# Sheet1_1.net
KiCad netlist of a schematic drawn in Altium Designer
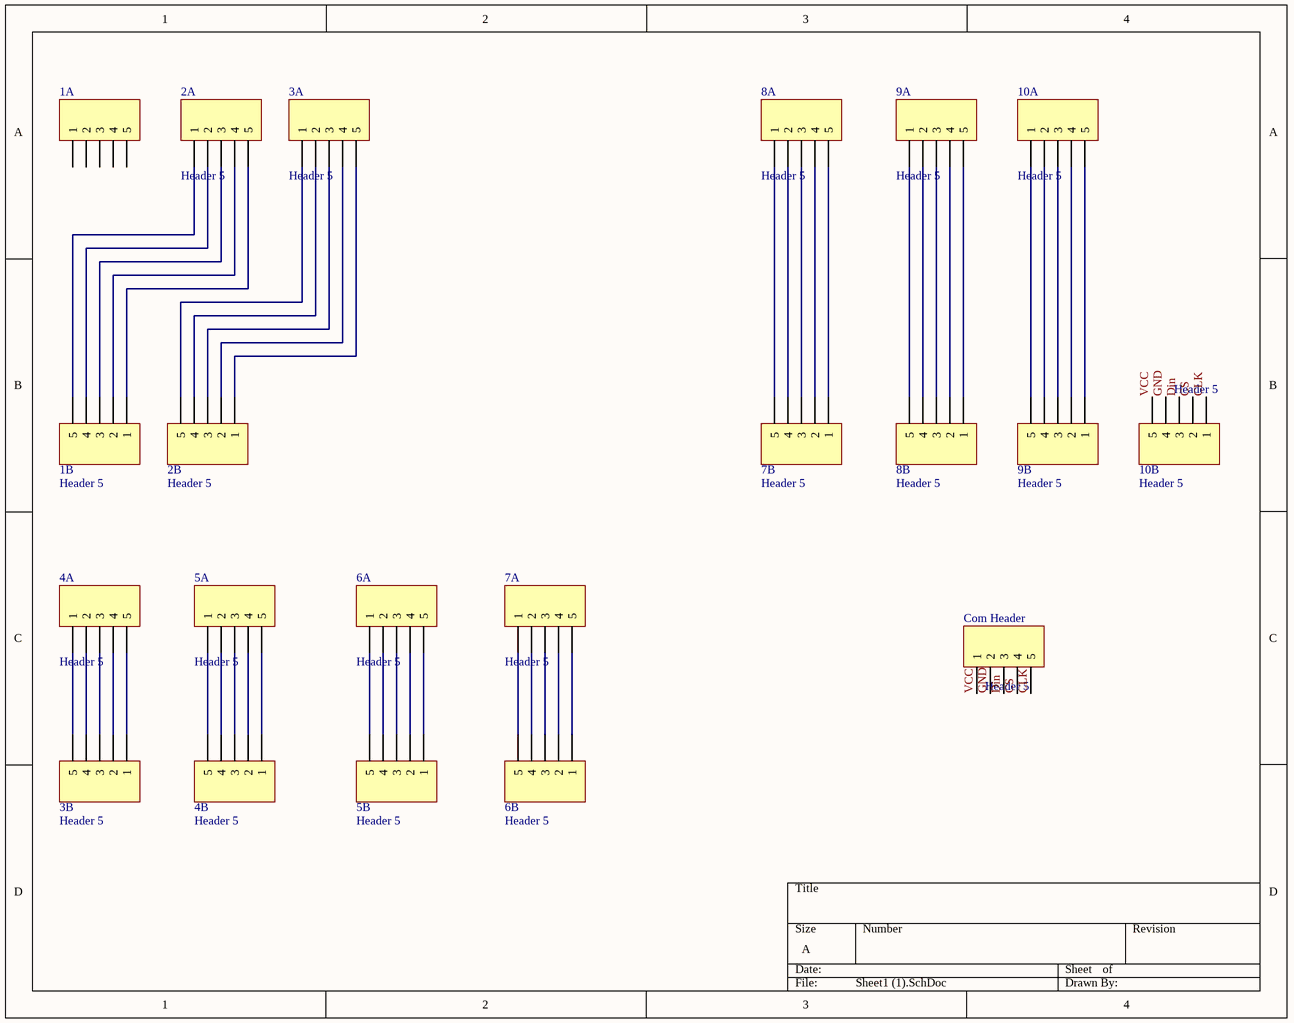
[diagram p0: Sheet1 (1).SchDoc]

(export (version "E")
  (design (tool "Eeschema 10.0.6"))
  (components
    (comp (ref "1A")
      (value "Header 5")
      (footprint "HDR1X5")
      (description "Header, 5-Pin")
      (fields (field (name "PUBLISHER") "Altium Limited"))
      (libsource (lib "Miscellaneous Connectors") (part "Header 5"))
    )
    (comp (ref "1B")
      (value "Header 5")
      (footprint "HDR1X5")
      (description "Header, 5-Pin")
      (fields (field (name "PUBLISHER") "Altium Limited"))
      (libsource (lib "") (part "Header 5_1"))
    )
    (comp (ref "2A")
      (value "Header 5")
      (footprint "HDR1X5")
      (description "Header, 5-Pin")
      (fields (field (name "PUBLISHER") "Altium Limited"))
      (libsource (lib "Miscellaneous Connectors") (part "Header 5"))
    )
    (comp (ref "2B")
      (value "Header 5")
      (footprint "HDR1X5")
      (description "Header, 5-Pin")
      (fields (field (name "PUBLISHER") "Altium Limited"))
      (libsource (lib "") (part "Header 5_1"))
    )
    (comp (ref "3A")
      (value "Header 5")
      (footprint "HDR1X5")
      (description "Header, 5-Pin")
      (fields (field (name "PUBLISHER") "Altium Limited"))
      (libsource (lib "Miscellaneous Connectors") (part "Header 5"))
    )
    (comp (ref "3B")
      (value "Header 5")
      (footprint "HDR1X5")
      (description "Header, 5-Pin")
      (fields (field (name "PUBLISHER") "Altium Limited"))
      (libsource (lib "") (part "Header 5_1"))
    )
    (comp (ref "4A")
      (value "Header 5")
      (footprint "HDR1X5")
      (description "Header, 5-Pin")
      (fields (field (name "PUBLISHER") "Altium Limited"))
      (libsource (lib "Miscellaneous Connectors") (part "Header 5"))
    )
    (comp (ref "4B")
      (value "Header 5")
      (footprint "HDR1X5")
      (description "Header, 5-Pin")
      (fields (field (name "PUBLISHER") "Altium Limited"))
      (libsource (lib "") (part "Header 5_1"))
    )
    (comp (ref "5A")
      (value "Header 5")
      (footprint "HDR1X5")
      (description "Header, 5-Pin")
      (fields (field (name "PUBLISHER") "Altium Limited"))
      (libsource (lib "Miscellaneous Connectors") (part "Header 5"))
    )
    (comp (ref "5B")
      (value "Header 5")
      (footprint "HDR1X5")
      (description "Header, 5-Pin")
      (fields (field (name "PUBLISHER") "Altium Limited"))
      (libsource (lib "") (part "Header 5_1"))
    )
    (comp (ref "6A")
      (value "Header 5")
      (footprint "HDR1X5")
      (description "Header, 5-Pin")
      (fields (field (name "PUBLISHER") "Altium Limited"))
      (libsource (lib "Miscellaneous Connectors") (part "Header 5"))
    )
    (comp (ref "6B")
      (value "Header 5")
      (footprint "HDR1X5")
      (description "Header, 5-Pin")
      (fields (field (name "PUBLISHER") "Altium Limited"))
      (libsource (lib "") (part "Header 5_1"))
    )
    (comp (ref "7A")
      (value "Header 5")
      (footprint "HDR1X5")
      (description "Header, 5-Pin")
      (fields (field (name "PUBLISHER") "Altium Limited"))
      (libsource (lib "Miscellaneous Connectors") (part "Header 5"))
    )
    (comp (ref "7B")
      (value "Header 5")
      (footprint "HDR1X5")
      (description "Header, 5-Pin")
      (fields (field (name "PUBLISHER") "Altium Limited"))
      (libsource (lib "") (part "Header 5_1"))
    )
    (comp (ref "8A")
      (value "Header 5")
      (footprint "HDR1X5")
      (description "Header, 5-Pin")
      (fields (field (name "PUBLISHER") "Altium Limited"))
      (libsource (lib "Miscellaneous Connectors") (part "Header 5"))
    )
    (comp (ref "8B")
      (value "Header 5")
      (footprint "HDR1X5")
      (description "Header, 5-Pin")
      (fields (field (name "PUBLISHER") "Altium Limited"))
      (libsource (lib "") (part "Header 5_1"))
    )
    (comp (ref "9A")
      (value "Header 5")
      (footprint "HDR1X5")
      (description "Header, 5-Pin")
      (fields (field (name "PUBLISHER") "Altium Limited"))
      (libsource (lib "Miscellaneous Connectors") (part "Header 5"))
    )
    (comp (ref "9B")
      (value "Header 5")
      (footprint "HDR1X5")
      (description "Header, 5-Pin")
      (fields (field (name "PUBLISHER") "Altium Limited"))
      (libsource (lib "") (part "Header 5_1"))
    )
    (comp (ref "10A")
      (value "Header 5")
      (footprint "HDR1X5")
      (description "Header, 5-Pin")
      (fields (field (name "PUBLISHER") "Altium Limited"))
      (libsource (lib "Miscellaneous Connectors") (part "Header 5"))
    )
    (comp (ref "10B")
      (value "Header 5")
      (footprint "HDR1X5")
      (description "Header, 5-Pin")
      (fields (field (name "PUBLISHER") "Altium Limited"))
      (libsource (lib "") (part "Header 5_1"))
    )
    (comp (ref "Com Header")
      (value "Header 5")
      (footprint "HDR1X5")
      (description "Header, 5-Pin")
      (fields (field (name "PUBLISHER") "Altium Limited"))
      (libsource (lib "Miscellaneous Connectors") (part "Header 5"))
    )
  )
  (nets
    (net (code "1") (name "/CLK") (class "Default")
      (node (ref "10B") (pin "1") (pinfunction "1_1") (pintype "passive"))
      (node (ref "Com Header") (pin "5") (pinfunction "5_5") (pintype "passive"))
    )
    (net (code "2") (name "/CS") (class "Default")
      (node (ref "10B") (pin "2") (pinfunction "2_2") (pintype "passive"))
      (node (ref "Com Header") (pin "4") (pinfunction "4_4") (pintype "passive"))
    )
    (net (code "3") (name "/Din") (class "Default")
      (node (ref "10B") (pin "3") (pinfunction "3_3") (pintype "passive"))
      (node (ref "Com Header") (pin "3") (pinfunction "3_3") (pintype "passive"))
    )
    (net (code "4") (name "/GND") (class "Default")
      (node (ref "10B") (pin "4") (pinfunction "4_4") (pintype "passive"))
      (node (ref "Com Header") (pin "2") (pinfunction "2_2") (pintype "passive"))
    )
    (net (code "5") (name "/VCC") (class "Default")
      (node (ref "10B") (pin "5") (pinfunction "5_5") (pintype "passive"))
      (node (ref "Com Header") (pin "1") (pinfunction "1_1") (pintype "passive"))
    )
    (net (code "6") (name "Net-(1B-Pad1)") (class "Default")
      (node (ref "1B") (pin "1") (pinfunction "1_1") (pintype "passive"))
      (node (ref "2A") (pin "5") (pinfunction "5_5") (pintype "passive"))
    )
    (net (code "7") (name "Net-(1B-Pad2)") (class "Default")
      (node (ref "1B") (pin "2") (pinfunction "2_2") (pintype "passive"))
      (node (ref "2A") (pin "4") (pinfunction "4_4") (pintype "passive"))
    )
    (net (code "8") (name "Net-(1B-Pad3)") (class "Default")
      (node (ref "1B") (pin "3") (pinfunction "3_3") (pintype "passive"))
      (node (ref "2A") (pin "3") (pinfunction "3_3") (pintype "passive"))
    )
    (net (code "9") (name "Net-(1B-Pad4)") (class "Default")
      (node (ref "1B") (pin "4") (pinfunction "4_4") (pintype "passive"))
      (node (ref "2A") (pin "2") (pinfunction "2_2") (pintype "passive"))
    )
    (net (code "10") (name "Net-(1B-Pad5)") (class "Default")
      (node (ref "1B") (pin "5") (pinfunction "5_5") (pintype "passive"))
      (node (ref "2A") (pin "1") (pinfunction "1_1") (pintype "passive"))
    )
    (net (code "11") (name "Net-(2B-Pad1)") (class "Default")
      (node (ref "2B") (pin "1") (pinfunction "1_1") (pintype "passive"))
      (node (ref "3A") (pin "5") (pinfunction "5_5") (pintype "passive"))
    )
    (net (code "12") (name "Net-(2B-Pad2)") (class "Default")
      (node (ref "2B") (pin "2") (pinfunction "2_2") (pintype "passive"))
      (node (ref "3A") (pin "4") (pinfunction "4_4") (pintype "passive"))
    )
    (net (code "13") (name "Net-(2B-Pad3)") (class "Default")
      (node (ref "2B") (pin "3") (pinfunction "3_3") (pintype "passive"))
      (node (ref "3A") (pin "3") (pinfunction "3_3") (pintype "passive"))
    )
    (net (code "14") (name "Net-(2B-Pad4)") (class "Default")
      (node (ref "2B") (pin "4") (pinfunction "4_4") (pintype "passive"))
      (node (ref "3A") (pin "2") (pinfunction "2_2") (pintype "passive"))
    )
    (net (code "15") (name "Net-(2B-Pad5)") (class "Default")
      (node (ref "2B") (pin "5") (pinfunction "5_5") (pintype "passive"))
      (node (ref "3A") (pin "1") (pinfunction "1_1") (pintype "passive"))
    )
    (net (code "16") (name "Net-(3B-Pad1)") (class "Default")
      (node (ref "3B") (pin "1") (pinfunction "1_1") (pintype "passive"))
      (node (ref "4A") (pin "5") (pinfunction "5_5") (pintype "passive"))
    )
    (net (code "17") (name "Net-(3B-Pad2)") (class "Default")
      (node (ref "3B") (pin "2") (pinfunction "2_2") (pintype "passive"))
      (node (ref "4A") (pin "4") (pinfunction "4_4") (pintype "passive"))
    )
    (net (code "18") (name "Net-(3B-Pad3)") (class "Default")
      (node (ref "3B") (pin "3") (pinfunction "3_3") (pintype "passive"))
      (node (ref "4A") (pin "3") (pinfunction "3_3") (pintype "passive"))
    )
    (net (code "19") (name "Net-(3B-Pad4)") (class "Default")
      (node (ref "3B") (pin "4") (pinfunction "4_4") (pintype "passive"))
      (node (ref "4A") (pin "2") (pinfunction "2_2") (pintype "passive"))
    )
    (net (code "20") (name "Net-(3B-Pad5)") (class "Default")
      (node (ref "3B") (pin "5") (pinfunction "5_5") (pintype "passive"))
      (node (ref "4A") (pin "1") (pinfunction "1_1") (pintype "passive"))
    )
    (net (code "21") (name "Net-(4B-Pad1)") (class "Default")
      (node (ref "4B") (pin "1") (pinfunction "1_1") (pintype "passive"))
      (node (ref "5A") (pin "5") (pinfunction "5_5") (pintype "passive"))
    )
    (net (code "22") (name "Net-(4B-Pad2)") (class "Default")
      (node (ref "4B") (pin "2") (pinfunction "2_2") (pintype "passive"))
      (node (ref "5A") (pin "4") (pinfunction "4_4") (pintype "passive"))
    )
    (net (code "23") (name "Net-(4B-Pad3)") (class "Default")
      (node (ref "4B") (pin "3") (pinfunction "3_3") (pintype "passive"))
      (node (ref "5A") (pin "3") (pinfunction "3_3") (pintype "passive"))
    )
    (net (code "24") (name "Net-(4B-Pad4)") (class "Default")
      (node (ref "4B") (pin "4") (pinfunction "4_4") (pintype "passive"))
      (node (ref "5A") (pin "2") (pinfunction "2_2") (pintype "passive"))
    )
    (net (code "25") (name "Net-(4B-Pad5)") (class "Default")
      (node (ref "4B") (pin "5") (pinfunction "5_5") (pintype "passive"))
      (node (ref "5A") (pin "1") (pinfunction "1_1") (pintype "passive"))
    )
    (net (code "26") (name "Net-(5B-Pad1)") (class "Default")
      (node (ref "5B") (pin "1") (pinfunction "1_1") (pintype "passive"))
      (node (ref "6A") (pin "5") (pinfunction "5_5") (pintype "passive"))
    )
    (net (code "27") (name "Net-(5B-Pad2)") (class "Default")
      (node (ref "5B") (pin "2") (pinfunction "2_2") (pintype "passive"))
      (node (ref "6A") (pin "4") (pinfunction "4_4") (pintype "passive"))
    )
    (net (code "28") (name "Net-(5B-Pad3)") (class "Default")
      (node (ref "5B") (pin "3") (pinfunction "3_3") (pintype "passive"))
      (node (ref "6A") (pin "3") (pinfunction "3_3") (pintype "passive"))
    )
    (net (code "29") (name "Net-(5B-Pad4)") (class "Default")
      (node (ref "5B") (pin "4") (pinfunction "4_4") (pintype "passive"))
      (node (ref "6A") (pin "2") (pinfunction "2_2") (pintype "passive"))
    )
    (net (code "30") (name "Net-(5B-Pad5)") (class "Default")
      (node (ref "5B") (pin "5") (pinfunction "5_5") (pintype "passive"))
      (node (ref "6A") (pin "1") (pinfunction "1_1") (pintype "passive"))
    )
    (net (code "31") (name "Net-(6B-Pad1)") (class "Default")
      (node (ref "6B") (pin "1") (pinfunction "1_1") (pintype "passive"))
      (node (ref "7A") (pin "5") (pinfunction "5_5") (pintype "passive"))
    )
    (net (code "32") (name "Net-(6B-Pad2)") (class "Default")
      (node (ref "6B") (pin "2") (pinfunction "2_2") (pintype "passive"))
      (node (ref "7A") (pin "4") (pinfunction "4_4") (pintype "passive"))
    )
    (net (code "33") (name "Net-(6B-Pad3)") (class "Default")
      (node (ref "6B") (pin "3") (pinfunction "3_3") (pintype "passive"))
      (node (ref "7A") (pin "3") (pinfunction "3_3") (pintype "passive"))
    )
    (net (code "34") (name "Net-(6B-Pad4)") (class "Default")
      (node (ref "6B") (pin "4") (pinfunction "4_4") (pintype "passive"))
      (node (ref "7A") (pin "2") (pinfunction "2_2") (pintype "passive"))
    )
    (net (code "35") (name "Net-(6B-Pad5)") (class "Default")
      (node (ref "6B") (pin "5") (pinfunction "5_5") (pintype "passive"))
      (node (ref "7A") (pin "1") (pinfunction "1_1") (pintype "passive"))
    )
    (net (code "36") (name "Net-(7B-Pad1)") (class "Default")
      (node (ref "7B") (pin "1") (pinfunction "1_1") (pintype "passive"))
      (node (ref "8A") (pin "5") (pinfunction "5_5") (pintype "passive"))
    )
    (net (code "37") (name "Net-(7B-Pad2)") (class "Default")
      (node (ref "7B") (pin "2") (pinfunction "2_2") (pintype "passive"))
      (node (ref "8A") (pin "4") (pinfunction "4_4") (pintype "passive"))
    )
    (net (code "38") (name "Net-(7B-Pad3)") (class "Default")
      (node (ref "7B") (pin "3") (pinfunction "3_3") (pintype "passive"))
      (node (ref "8A") (pin "3") (pinfunction "3_3") (pintype "passive"))
    )
    (net (code "39") (name "Net-(7B-Pad4)") (class "Default")
      (node (ref "7B") (pin "4") (pinfunction "4_4") (pintype "passive"))
      (node (ref "8A") (pin "2") (pinfunction "2_2") (pintype "passive"))
    )
    (net (code "40") (name "Net-(7B-Pad5)") (class "Default")
      (node (ref "7B") (pin "5") (pinfunction "5_5") (pintype "passive"))
      (node (ref "8A") (pin "1") (pinfunction "1_1") (pintype "passive"))
    )
    (net (code "41") (name "Net-(8B-Pad1)") (class "Default")
      (node (ref "8B") (pin "1") (pinfunction "1_1") (pintype "passive"))
      (node (ref "9A") (pin "5") (pinfunction "5_5") (pintype "passive"))
    )
    (net (code "42") (name "Net-(8B-Pad2)") (class "Default")
      (node (ref "8B") (pin "2") (pinfunction "2_2") (pintype "passive"))
      (node (ref "9A") (pin "4") (pinfunction "4_4") (pintype "passive"))
    )
    (net (code "43") (name "Net-(8B-Pad3)") (class "Default")
      (node (ref "8B") (pin "3") (pinfunction "3_3") (pintype "passive"))
      (node (ref "9A") (pin "3") (pinfunction "3_3") (pintype "passive"))
    )
    (net (code "44") (name "Net-(8B-Pad4)") (class "Default")
      (node (ref "8B") (pin "4") (pinfunction "4_4") (pintype "passive"))
      (node (ref "9A") (pin "2") (pinfunction "2_2") (pintype "passive"))
    )
    (net (code "45") (name "Net-(8B-Pad5)") (class "Default")
      (node (ref "8B") (pin "5") (pinfunction "5_5") (pintype "passive"))
      (node (ref "9A") (pin "1") (pinfunction "1_1") (pintype "passive"))
    )
    (net (code "46") (name "Net-(10A-Pad1)") (class "Default")
      (node (ref "10A") (pin "1") (pinfunction "1_1") (pintype "passive"))
      (node (ref "9B") (pin "5") (pinfunction "5_5") (pintype "passive"))
    )
    (net (code "47") (name "Net-(10A-Pad2)") (class "Default")
      (node (ref "10A") (pin "2") (pinfunction "2_2") (pintype "passive"))
      (node (ref "9B") (pin "4") (pinfunction "4_4") (pintype "passive"))
    )
    (net (code "48") (name "Net-(10A-Pad3)") (class "Default")
      (node (ref "10A") (pin "3") (pinfunction "3_3") (pintype "passive"))
      (node (ref "9B") (pin "3") (pinfunction "3_3") (pintype "passive"))
    )
    (net (code "49") (name "Net-(10A-Pad4)") (class "Default")
      (node (ref "10A") (pin "4") (pinfunction "4_4") (pintype "passive"))
      (node (ref "9B") (pin "2") (pinfunction "2_2") (pintype "passive"))
    )
    (net (code "50") (name "Net-(10A-Pad5)") (class "Default")
      (node (ref "10A") (pin "5") (pinfunction "5_5") (pintype "passive"))
      (node (ref "9B") (pin "1") (pinfunction "1_1") (pintype "passive"))
    )
    (net (code "51") (name "unconnected-(1A-Pad1)") (class "Default")
      (node (ref "1A") (pin "1") (pinfunction "1_1") (pintype "passive"))
    )
    (net (code "52") (name "unconnected-(1A-Pad2)") (class "Default")
      (node (ref "1A") (pin "2") (pinfunction "2_2") (pintype "passive"))
    )
    (net (code "53") (name "unconnected-(1A-Pad3)") (class "Default")
      (node (ref "1A") (pin "3") (pinfunction "3_3") (pintype "passive"))
    )
    (net (code "54") (name "unconnected-(1A-Pad4)") (class "Default")
      (node (ref "1A") (pin "4") (pinfunction "4_4") (pintype "passive"))
    )
    (net (code "55") (name "unconnected-(1A-Pad5)") (class "Default")
      (node (ref "1A") (pin "5") (pinfunction "5_5") (pintype "passive"))
    )
  )
)
